# Token.net
KiCad netlist of a schematic drawn in EAGLE
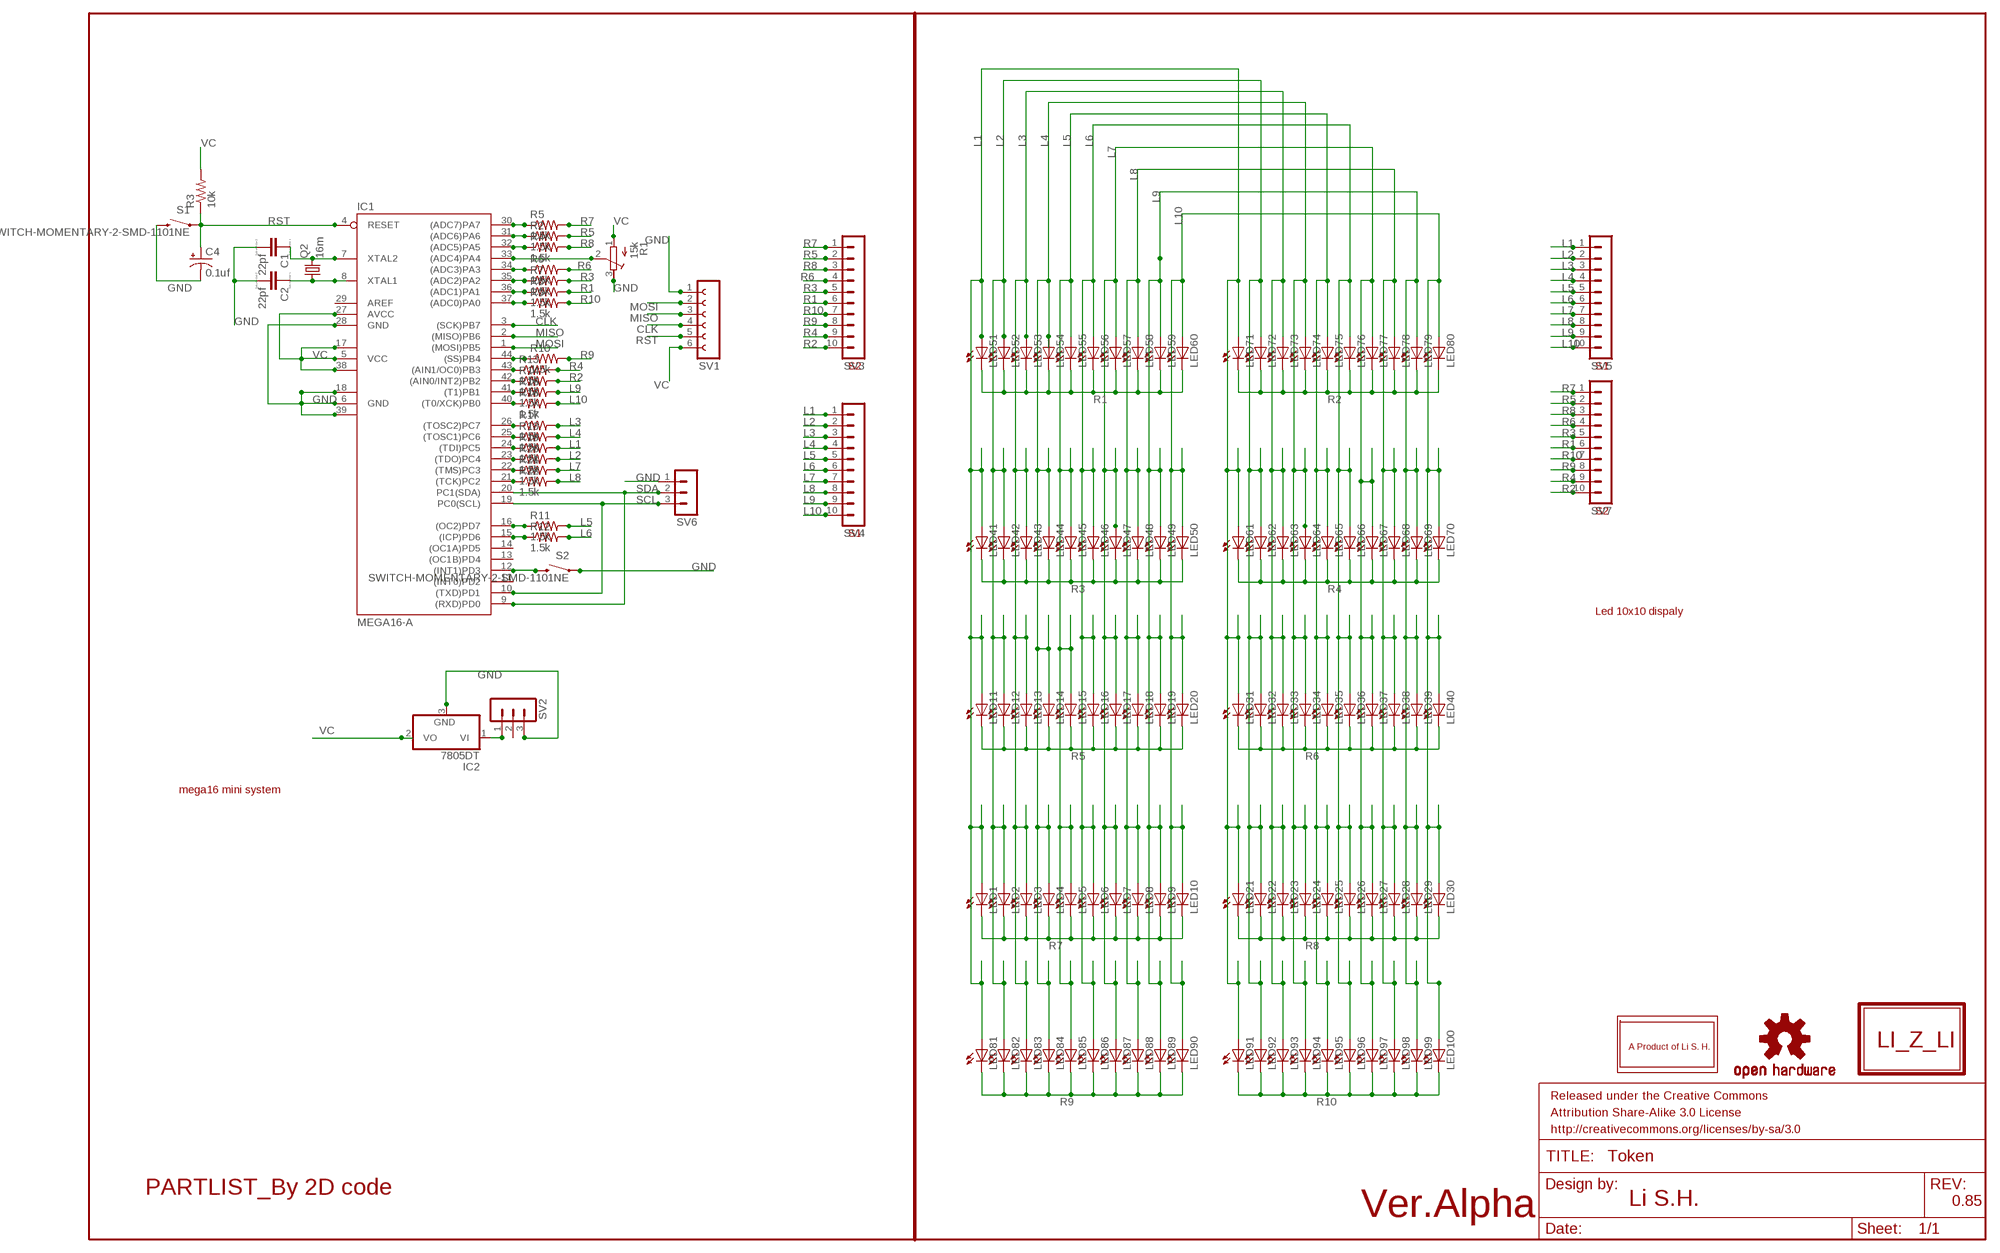
[diagram p0: schematic, sheet 1]

(export (version "E")
  (design (tool "Eeschema 10.0.6"))
  (components
    (comp (ref "C1")
      (value "22pf")
      (footprint "eagle-import:C0402")
      (libsource (lib "eagle-import") (part "CC0402"))
    )
    (comp (ref "C2")
      (value "22pf")
      (footprint "eagle-import:C0402")
      (libsource (lib "eagle-import") (part "CC0402"))
    )
    (comp (ref "C4")
      (value "0.1uf")
      (footprint "eagle-import:D_7343-31W")
      (libsource (lib "eagle-import") (part "CPOL-USD/7343-31W"))
    )
    (comp (ref "FRAME1")
      (value "FRAME-LEDGER")
      (footprint "eagle-import:CREATIVE_COMMONS")
      (libsource (lib "eagle-import") (part "FRAME-LEDGER"))
    )
    (comp (ref "IC1")
      (value "MEGA16-A")
      (footprint "eagle-import:TQFP44")
      (fields (field (name "MPN") "ATMEGA16-16AU"))
      (libsource (lib "eagle-import") (part "MEGA16-A"))
    )
    (comp (ref "IC2")
      (value "7805DT")
      (footprint "eagle-import:TO252")
      (libsource (lib "eagle-import") (part "78DT05"))
    )
    (comp (ref "LED1")
      (value "LEDCHIPLED_0805")
      (footprint "eagle-import:CHIPLED_0805")
      (libsource (lib "eagle-import") (part "LEDCHIPLED_0805"))
    )
    (comp (ref "LED2")
      (value "LEDCHIPLED_0805")
      (footprint "eagle-import:CHIPLED_0805")
      (libsource (lib "eagle-import") (part "LEDCHIPLED_0805"))
    )
    (comp (ref "LED3")
      (value "LEDCHIPLED_0805")
      (footprint "eagle-import:CHIPLED_0805")
      (libsource (lib "eagle-import") (part "LEDCHIPLED_0805"))
    )
    (comp (ref "LED4")
      (value "LEDCHIPLED_0805")
      (footprint "eagle-import:CHIPLED_0805")
      (libsource (lib "eagle-import") (part "LEDCHIPLED_0805"))
    )
    (comp (ref "LED5")
      (value "LEDCHIPLED_0805")
      (footprint "eagle-import:CHIPLED_0805")
      (libsource (lib "eagle-import") (part "LEDCHIPLED_0805"))
    )
    (comp (ref "LED6")
      (value "LEDCHIPLED_0805")
      (footprint "eagle-import:CHIPLED_0805")
      (libsource (lib "eagle-import") (part "LEDCHIPLED_0805"))
    )
    (comp (ref "LED7")
      (value "LEDCHIPLED_0805")
      (footprint "eagle-import:CHIPLED_0805")
      (libsource (lib "eagle-import") (part "LEDCHIPLED_0805"))
    )
    (comp (ref "LED8")
      (value "LEDCHIPLED_0805")
      (footprint "eagle-import:CHIPLED_0805")
      (libsource (lib "eagle-import") (part "LEDCHIPLED_0805"))
    )
    (comp (ref "LED9")
      (value "LEDCHIPLED_0805")
      (footprint "eagle-import:CHIPLED_0805")
      (libsource (lib "eagle-import") (part "LEDCHIPLED_0805"))
    )
    (comp (ref "LED10")
      (value "LEDCHIPLED_0805")
      (footprint "eagle-import:CHIPLED_0805")
      (libsource (lib "eagle-import") (part "LEDCHIPLED_0805"))
    )
    (comp (ref "LED11")
      (value "LEDCHIPLED_0805")
      (footprint "eagle-import:CHIPLED_0805")
      (libsource (lib "eagle-import") (part "LEDCHIPLED_0805"))
    )
    (comp (ref "LED12")
      (value "LEDCHIPLED_0805")
      (footprint "eagle-import:CHIPLED_0805")
      (libsource (lib "eagle-import") (part "LEDCHIPLED_0805"))
    )
    (comp (ref "LED13")
      (value "LEDCHIPLED_0805")
      (footprint "eagle-import:CHIPLED_0805")
      (libsource (lib "eagle-import") (part "LEDCHIPLED_0805"))
    )
    (comp (ref "LED14")
      (value "LEDCHIPLED_0805")
      (footprint "eagle-import:CHIPLED_0805")
      (libsource (lib "eagle-import") (part "LEDCHIPLED_0805"))
    )
    (comp (ref "LED15")
      (value "LEDCHIPLED_0805")
      (footprint "eagle-import:CHIPLED_0805")
      (libsource (lib "eagle-import") (part "LEDCHIPLED_0805"))
    )
    (comp (ref "LED16")
      (value "LEDCHIPLED_0805")
      (footprint "eagle-import:CHIPLED_0805")
      (libsource (lib "eagle-import") (part "LEDCHIPLED_0805"))
    )
    (comp (ref "LED17")
      (value "LEDCHIPLED_0805")
      (footprint "eagle-import:CHIPLED_0805")
      (libsource (lib "eagle-import") (part "LEDCHIPLED_0805"))
    )
    (comp (ref "LED18")
      (value "LEDCHIPLED_0805")
      (footprint "eagle-import:CHIPLED_0805")
      (libsource (lib "eagle-import") (part "LEDCHIPLED_0805"))
    )
    (comp (ref "LED19")
      (value "LEDCHIPLED_0805")
      (footprint "eagle-import:CHIPLED_0805")
      (libsource (lib "eagle-import") (part "LEDCHIPLED_0805"))
    )
    (comp (ref "LED20")
      (value "LEDCHIPLED_0805")
      (footprint "eagle-import:CHIPLED_0805")
      (libsource (lib "eagle-import") (part "LEDCHIPLED_0805"))
    )
    (comp (ref "LED21")
      (value "LEDCHIPLED_0805")
      (footprint "eagle-import:CHIPLED_0805")
      (libsource (lib "eagle-import") (part "LEDCHIPLED_0805"))
    )
    (comp (ref "LED22")
      (value "LEDCHIPLED_0805")
      (footprint "eagle-import:CHIPLED_0805")
      (libsource (lib "eagle-import") (part "LEDCHIPLED_0805"))
    )
    (comp (ref "LED23")
      (value "LEDCHIPLED_0805")
      (footprint "eagle-import:CHIPLED_0805")
      (libsource (lib "eagle-import") (part "LEDCHIPLED_0805"))
    )
    (comp (ref "LED24")
      (value "LEDCHIPLED_0805")
      (footprint "eagle-import:CHIPLED_0805")
      (libsource (lib "eagle-import") (part "LEDCHIPLED_0805"))
    )
    (comp (ref "LED25")
      (value "LEDCHIPLED_0805")
      (footprint "eagle-import:CHIPLED_0805")
      (libsource (lib "eagle-import") (part "LEDCHIPLED_0805"))
    )
    (comp (ref "LED26")
      (value "LEDCHIPLED_0805")
      (footprint "eagle-import:CHIPLED_0805")
      (libsource (lib "eagle-import") (part "LEDCHIPLED_0805"))
    )
    (comp (ref "LED27")
      (value "LEDCHIPLED_0805")
      (footprint "eagle-import:CHIPLED_0805")
      (libsource (lib "eagle-import") (part "LEDCHIPLED_0805"))
    )
    (comp (ref "LED28")
      (value "LEDCHIPLED_0805")
      (footprint "eagle-import:CHIPLED_0805")
      (libsource (lib "eagle-import") (part "LEDCHIPLED_0805"))
    )
    (comp (ref "LED29")
      (value "LEDCHIPLED_0805")
      (footprint "eagle-import:CHIPLED_0805")
      (libsource (lib "eagle-import") (part "LEDCHIPLED_0805"))
    )
    (comp (ref "LED30")
      (value "LEDCHIPLED_0805")
      (footprint "eagle-import:CHIPLED_0805")
      (libsource (lib "eagle-import") (part "LEDCHIPLED_0805"))
    )
    (comp (ref "LED31")
      (value "LEDCHIPLED_0805")
      (footprint "eagle-import:CHIPLED_0805")
      (libsource (lib "eagle-import") (part "LEDCHIPLED_0805"))
    )
    (comp (ref "LED32")
      (value "LEDCHIPLED_0805")
      (footprint "eagle-import:CHIPLED_0805")
      (libsource (lib "eagle-import") (part "LEDCHIPLED_0805"))
    )
    (comp (ref "LED33")
      (value "LEDCHIPLED_0805")
      (footprint "eagle-import:CHIPLED_0805")
      (libsource (lib "eagle-import") (part "LEDCHIPLED_0805"))
    )
    (comp (ref "LED34")
      (value "LEDCHIPLED_0805")
      (footprint "eagle-import:CHIPLED_0805")
      (libsource (lib "eagle-import") (part "LEDCHIPLED_0805"))
    )
    (comp (ref "LED35")
      (value "LEDCHIPLED_0805")
      (footprint "eagle-import:CHIPLED_0805")
      (libsource (lib "eagle-import") (part "LEDCHIPLED_0805"))
    )
    (comp (ref "LED36")
      (value "LEDCHIPLED_0805")
      (footprint "eagle-import:CHIPLED_0805")
      (libsource (lib "eagle-import") (part "LEDCHIPLED_0805"))
    )
    (comp (ref "LED37")
      (value "LEDCHIPLED_0805")
      (footprint "eagle-import:CHIPLED_0805")
      (libsource (lib "eagle-import") (part "LEDCHIPLED_0805"))
    )
    (comp (ref "LED38")
      (value "LEDCHIPLED_0805")
      (footprint "eagle-import:CHIPLED_0805")
      (libsource (lib "eagle-import") (part "LEDCHIPLED_0805"))
    )
    (comp (ref "LED39")
      (value "LEDCHIPLED_0805")
      (footprint "eagle-import:CHIPLED_0805")
      (libsource (lib "eagle-import") (part "LEDCHIPLED_0805"))
    )
    (comp (ref "LED40")
      (value "LEDCHIPLED_0805")
      (footprint "eagle-import:CHIPLED_0805")
      (libsource (lib "eagle-import") (part "LEDCHIPLED_0805"))
    )
    (comp (ref "LED41")
      (value "LEDCHIPLED_0805")
      (footprint "eagle-import:CHIPLED_0805")
      (libsource (lib "eagle-import") (part "LEDCHIPLED_0805"))
    )
    (comp (ref "LED42")
      (value "LEDCHIPLED_0805")
      (footprint "eagle-import:CHIPLED_0805")
      (libsource (lib "eagle-import") (part "LEDCHIPLED_0805"))
    )
    (comp (ref "LED43")
      (value "LEDCHIPLED_0805")
      (footprint "eagle-import:CHIPLED_0805")
      (libsource (lib "eagle-import") (part "LEDCHIPLED_0805"))
    )
    (comp (ref "LED44")
      (value "LEDCHIPLED_0805")
      (footprint "eagle-import:CHIPLED_0805")
      (libsource (lib "eagle-import") (part "LEDCHIPLED_0805"))
    )
    (comp (ref "LED45")
      (value "LEDCHIPLED_0805")
      (footprint "eagle-import:CHIPLED_0805")
      (libsource (lib "eagle-import") (part "LEDCHIPLED_0805"))
    )
    (comp (ref "LED46")
      (value "LEDCHIPLED_0805")
      (footprint "eagle-import:CHIPLED_0805")
      (libsource (lib "eagle-import") (part "LEDCHIPLED_0805"))
    )
    (comp (ref "LED47")
      (value "LEDCHIPLED_0805")
      (footprint "eagle-import:CHIPLED_0805")
      (libsource (lib "eagle-import") (part "LEDCHIPLED_0805"))
    )
    (comp (ref "LED48")
      (value "LEDCHIPLED_0805")
      (footprint "eagle-import:CHIPLED_0805")
      (libsource (lib "eagle-import") (part "LEDCHIPLED_0805"))
    )
    (comp (ref "LED49")
      (value "LEDCHIPLED_0805")
      (footprint "eagle-import:CHIPLED_0805")
      (libsource (lib "eagle-import") (part "LEDCHIPLED_0805"))
    )
    (comp (ref "LED50")
      (value "LEDCHIPLED_0805")
      (footprint "eagle-import:CHIPLED_0805")
      (libsource (lib "eagle-import") (part "LEDCHIPLED_0805"))
    )
    (comp (ref "LED51")
      (value "LEDCHIPLED_0805")
      (footprint "eagle-import:CHIPLED_0805")
      (libsource (lib "eagle-import") (part "LEDCHIPLED_0805"))
    )
    (comp (ref "LED52")
      (value "LEDCHIPLED_0805")
      (footprint "eagle-import:CHIPLED_0805")
      (libsource (lib "eagle-import") (part "LEDCHIPLED_0805"))
    )
    (comp (ref "LED53")
      (value "LEDCHIPLED_0805")
      (footprint "eagle-import:CHIPLED_0805")
      (libsource (lib "eagle-import") (part "LEDCHIPLED_0805"))
    )
    (comp (ref "LED54")
      (value "LEDCHIPLED_0805")
      (footprint "eagle-import:CHIPLED_0805")
      (libsource (lib "eagle-import") (part "LEDCHIPLED_0805"))
    )
    (comp (ref "LED55")
      (value "LEDCHIPLED_0805")
      (footprint "eagle-import:CHIPLED_0805")
      (libsource (lib "eagle-import") (part "LEDCHIPLED_0805"))
    )
    (comp (ref "LED56")
      (value "LEDCHIPLED_0805")
      (footprint "eagle-import:CHIPLED_0805")
      (libsource (lib "eagle-import") (part "LEDCHIPLED_0805"))
    )
    (comp (ref "LED57")
      (value "LEDCHIPLED_0805")
      (footprint "eagle-import:CHIPLED_0805")
      (libsource (lib "eagle-import") (part "LEDCHIPLED_0805"))
    )
    (comp (ref "LED58")
      (value "LEDCHIPLED_0805")
      (footprint "eagle-import:CHIPLED_0805")
      (libsource (lib "eagle-import") (part "LEDCHIPLED_0805"))
    )
    (comp (ref "LED59")
      (value "LEDCHIPLED_0805")
      (footprint "eagle-import:CHIPLED_0805")
      (libsource (lib "eagle-import") (part "LEDCHIPLED_0805"))
    )
    (comp (ref "LED60")
      (value "LEDCHIPLED_0805")
      (footprint "eagle-import:CHIPLED_0805")
      (libsource (lib "eagle-import") (part "LEDCHIPLED_0805"))
    )
    (comp (ref "LED61")
      (value "LEDCHIPLED_0805")
      (footprint "eagle-import:CHIPLED_0805")
      (libsource (lib "eagle-import") (part "LEDCHIPLED_0805"))
    )
    (comp (ref "LED62")
      (value "LEDCHIPLED_0805")
      (footprint "eagle-import:CHIPLED_0805")
      (libsource (lib "eagle-import") (part "LEDCHIPLED_0805"))
    )
    (comp (ref "LED63")
      (value "LEDCHIPLED_0805")
      (footprint "eagle-import:CHIPLED_0805")
      (libsource (lib "eagle-import") (part "LEDCHIPLED_0805"))
    )
    (comp (ref "LED64")
      (value "LEDCHIPLED_0805")
      (footprint "eagle-import:CHIPLED_0805")
      (libsource (lib "eagle-import") (part "LEDCHIPLED_0805"))
    )
    (comp (ref "LED65")
      (value "LEDCHIPLED_0805")
      (footprint "eagle-import:CHIPLED_0805")
      (libsource (lib "eagle-import") (part "LEDCHIPLED_0805"))
    )
    (comp (ref "LED66")
      (value "LEDCHIPLED_0805")
      (footprint "eagle-import:CHIPLED_0805")
      (libsource (lib "eagle-import") (part "LEDCHIPLED_0805"))
    )
    (comp (ref "LED67")
      (value "LEDCHIPLED_0805")
      (footprint "eagle-import:CHIPLED_0805")
      (libsource (lib "eagle-import") (part "LEDCHIPLED_0805"))
    )
    (comp (ref "LED68")
      (value "LEDCHIPLED_0805")
      (footprint "eagle-import:CHIPLED_0805")
      (libsource (lib "eagle-import") (part "LEDCHIPLED_0805"))
    )
    (comp (ref "LED69")
      (value "LEDCHIPLED_0805")
      (footprint "eagle-import:CHIPLED_0805")
      (libsource (lib "eagle-import") (part "LEDCHIPLED_0805"))
    )
    (comp (ref "LED70")
      (value "LEDCHIPLED_0805")
      (footprint "eagle-import:CHIPLED_0805")
      (libsource (lib "eagle-import") (part "LEDCHIPLED_0805"))
    )
    (comp (ref "LED71")
      (value "LEDCHIPLED_0805")
      (footprint "eagle-import:CHIPLED_0805")
      (libsource (lib "eagle-import") (part "LEDCHIPLED_0805"))
    )
    (comp (ref "LED72")
      (value "LEDCHIPLED_0805")
      (footprint "eagle-import:CHIPLED_0805")
      (libsource (lib "eagle-import") (part "LEDCHIPLED_0805"))
    )
    (comp (ref "LED73")
      (value "LEDCHIPLED_0805")
      (footprint "eagle-import:CHIPLED_0805")
      (libsource (lib "eagle-import") (part "LEDCHIPLED_0805"))
    )
    (comp (ref "LED74")
      (value "LEDCHIPLED_0805")
      (footprint "eagle-import:CHIPLED_0805")
      (libsource (lib "eagle-import") (part "LEDCHIPLED_0805"))
    )
    (comp (ref "LED75")
      (value "LEDCHIPLED_0805")
      (footprint "eagle-import:CHIPLED_0805")
      (libsource (lib "eagle-import") (part "LEDCHIPLED_0805"))
    )
    (comp (ref "LED76")
      (value "LEDCHIPLED_0805")
      (footprint "eagle-import:CHIPLED_0805")
      (libsource (lib "eagle-import") (part "LEDCHIPLED_0805"))
    )
    (comp (ref "LED77")
      (value "LEDCHIPLED_0805")
      (footprint "eagle-import:CHIPLED_0805")
      (libsource (lib "eagle-import") (part "LEDCHIPLED_0805"))
    )
    (comp (ref "LED78")
      (value "LEDCHIPLED_0805")
      (footprint "eagle-import:CHIPLED_0805")
      (libsource (lib "eagle-import") (part "LEDCHIPLED_0805"))
    )
    (comp (ref "LED79")
      (value "LEDCHIPLED_0805")
      (footprint "eagle-import:CHIPLED_0805")
      (libsource (lib "eagle-import") (part "LEDCHIPLED_0805"))
    )
    (comp (ref "LED80")
      (value "LEDCHIPLED_0805")
      (footprint "eagle-import:CHIPLED_0805")
      (libsource (lib "eagle-import") (part "LEDCHIPLED_0805"))
    )
    (comp (ref "LED81")
      (value "LEDCHIPLED_0805")
      (footprint "eagle-import:CHIPLED_0805")
      (libsource (lib "eagle-import") (part "LEDCHIPLED_0805"))
    )
    (comp (ref "LED82")
      (value "LEDCHIPLED_0805")
      (footprint "eagle-import:CHIPLED_0805")
      (libsource (lib "eagle-import") (part "LEDCHIPLED_0805"))
    )
    (comp (ref "LED83")
      (value "LEDCHIPLED_0805")
      (footprint "eagle-import:CHIPLED_0805")
      (libsource (lib "eagle-import") (part "LEDCHIPLED_0805"))
    )
    (comp (ref "LED84")
      (value "LEDCHIPLED_0805")
      (footprint "eagle-import:CHIPLED_0805")
      (libsource (lib "eagle-import") (part "LEDCHIPLED_0805"))
    )
    (comp (ref "LED85")
      (value "LEDCHIPLED_0805")
      (footprint "eagle-import:CHIPLED_0805")
      (libsource (lib "eagle-import") (part "LEDCHIPLED_0805"))
    )
    (comp (ref "LED86")
      (value "LEDCHIPLED_0805")
      (footprint "eagle-import:CHIPLED_0805")
      (libsource (lib "eagle-import") (part "LEDCHIPLED_0805"))
    )
    (comp (ref "LED87")
      (value "LEDCHIPLED_0805")
      (footprint "eagle-import:CHIPLED_0805")
      (libsource (lib "eagle-import") (part "LEDCHIPLED_0805"))
    )
    (comp (ref "LED88")
      (value "LEDCHIPLED_0805")
      (footprint "eagle-import:CHIPLED_0805")
      (libsource (lib "eagle-import") (part "LEDCHIPLED_0805"))
    )
    (comp (ref "LED89")
      (value "LEDCHIPLED_0805")
      (footprint "eagle-import:CHIPLED_0805")
      (libsource (lib "eagle-import") (part "LEDCHIPLED_0805"))
    )
    (comp (ref "LED90")
      (value "LEDCHIPLED_0805")
      (footprint "eagle-import:CHIPLED_0805")
      (libsource (lib "eagle-import") (part "LEDCHIPLED_0805"))
    )
    (comp (ref "LED91")
      (value "LEDCHIPLED_0805")
      (footprint "eagle-import:CHIPLED_0805")
      (libsource (lib "eagle-import") (part "LEDCHIPLED_0805"))
    )
    (comp (ref "LED92")
      (value "LEDCHIPLED_0805")
      (footprint "eagle-import:CHIPLED_0805")
      (libsource (lib "eagle-import") (part "LEDCHIPLED_0805"))
    )
    (comp (ref "LED93")
      (value "LEDCHIPLED_0805")
      (footprint "eagle-import:CHIPLED_0805")
      (libsource (lib "eagle-import") (part "LEDCHIPLED_0805"))
    )
    (comp (ref "LED94")
      (value "LEDCHIPLED_0805")
      (footprint "eagle-import:CHIPLED_0805")
      (libsource (lib "eagle-import") (part "LEDCHIPLED_0805"))
    )
    (comp (ref "LED95")
      (value "LEDCHIPLED_0805")
      (footprint "eagle-import:CHIPLED_0805")
      (libsource (lib "eagle-import") (part "LEDCHIPLED_0805"))
    )
    (comp (ref "LED96")
      (value "LEDCHIPLED_0805")
      (footprint "eagle-import:CHIPLED_0805")
      (libsource (lib "eagle-import") (part "LEDCHIPLED_0805"))
    )
    (comp (ref "LED97")
      (value "LEDCHIPLED_0805")
      (footprint "eagle-import:CHIPLED_0805")
      (libsource (lib "eagle-import") (part "LEDCHIPLED_0805"))
    )
    (comp (ref "LED98")
      (value "LEDCHIPLED_0805")
      (footprint "eagle-import:CHIPLED_0805")
      (libsource (lib "eagle-import") (part "LEDCHIPLED_0805"))
    )
    (comp (ref "LED99")
      (value "LEDCHIPLED_0805")
      (footprint "eagle-import:CHIPLED_0805")
      (libsource (lib "eagle-import") (part "LEDCHIPLED_0805"))
    )
    (comp (ref "LED100")
      (value "LEDCHIPLED_0805")
      (footprint "eagle-import:CHIPLED_0805")
      (libsource (lib "eagle-import") (part "LEDCHIPLED_0805"))
    )
    (comp (ref "LOGO1")
      (value "OSHW-LOGOS")
      (footprint "eagle-import:OSHW-LOGO-S")
      (libsource (lib "eagle-import") (part "OSHW-LOGOS"))
    )
    (comp (ref "Q2")
      (value "16m")
      (footprint "eagle-import:HC49UP")
      (libsource (lib "eagle-import") (part "CRYSTALHC49UP"))
    )
    (comp (ref "R1")
      (value "15k")
      (footprint "eagle-import:RTRIM64W")
      (libsource (lib "eagle-import") (part "R-TRIMM64W"))
    )
    (comp (ref "R2")
      (value "1.5k")
      (footprint "eagle-import:R0201")
      (libsource (lib "eagle-import") (part "R-US_R0201"))
    )
    (comp (ref "R3")
      (value "10k")
      (footprint "eagle-import:R0201")
      (libsource (lib "eagle-import") (part "R-US_R0201"))
    )
    (comp (ref "R4")
      (value "1.5k")
      (footprint "eagle-import:R0201")
      (libsource (lib "eagle-import") (part "R-US_R0201"))
    )
    (comp (ref "R5")
      (value "1.5k")
      (footprint "eagle-import:R0201")
      (libsource (lib "eagle-import") (part "R-US_R0201"))
    )
    (comp (ref "R6")
      (value "1.5k")
      (footprint "eagle-import:R0201")
      (libsource (lib "eagle-import") (part "R-US_R0201"))
    )
    (comp (ref "R7")
      (value "1.5k")
      (footprint "eagle-import:R0201")
      (libsource (lib "eagle-import") (part "R-US_R0201"))
    )
    (comp (ref "R8")
      (value "1.5k")
      (footprint "eagle-import:R0201")
      (libsource (lib "eagle-import") (part "R-US_R0201"))
    )
    (comp (ref "R9")
      (value "1.5k")
      (footprint "eagle-import:R0201")
      (libsource (lib "eagle-import") (part "R-US_R0201"))
    )
    (comp (ref "R10")
      (value "1.5k")
      (footprint "eagle-import:R0201")
      (libsource (lib "eagle-import") (part "R-US_R0201"))
    )
    (comp (ref "R11")
      (value "1.5k")
      (footprint "eagle-import:R0201")
      (libsource (lib "eagle-import") (part "R-US_R0201"))
    )
    (comp (ref "R12")
      (value "1.5k")
      (footprint "eagle-import:R0201")
      (libsource (lib "eagle-import") (part "R-US_R0201"))
    )
    (comp (ref "R13")
      (value "1.5k")
      (footprint "eagle-import:R0201")
      (libsource (lib "eagle-import") (part "R-US_R0201"))
    )
    (comp (ref "R14")
      (value "1.5k")
      (footprint "eagle-import:R0201")
      (libsource (lib "eagle-import") (part "R-US_R0201"))
    )
    (comp (ref "R15")
      (value "1.5k")
      (footprint "eagle-import:R0201")
      (libsource (lib "eagle-import") (part "R-US_R0201"))
    )
    (comp (ref "R16")
      (value "1.5k")
      (footprint "eagle-import:R0201")
      (libsource (lib "eagle-import") (part "R-US_R0201"))
    )
    (comp (ref "R17")
      (value "1.5k")
      (footprint "eagle-import:R0201")
      (libsource (lib "eagle-import") (part "R-US_R0201"))
    )
    (comp (ref "R18")
      (value "1.5k")
      (footprint "eagle-import:R0201")
      (libsource (lib "eagle-import") (part "R-US_R0201"))
    )
    (comp (ref "R19")
      (value "1.5k")
      (footprint "eagle-import:R0201")
      (libsource (lib "eagle-import") (part "R-US_R0201"))
    )
    (comp (ref "R20")
      (value "1.5k")
      (footprint "eagle-import:R0201")
      (libsource (lib "eagle-import") (part "R-US_R0201"))
    )
    (comp (ref "R21")
      (value "1.5k")
      (footprint "eagle-import:R0201")
      (libsource (lib "eagle-import") (part "R-US_R0201"))
    )
    (comp (ref "R22")
      (value "1.5k")
      (footprint "eagle-import:R0201")
      (libsource (lib "eagle-import") (part "R-US_R0201"))
    )
    (comp (ref "S1")
      (value "SWITCH-MOMENTARY-2-SMD-1101NE")
      (footprint "eagle-import:TACTILE-SWITCH-1101NE")
      (libsource (lib "eagle-import") (part "SWITCH-MOMENTARY-2-SMD-1101NE"))
    )
    (comp (ref "S2")
      (value "SWITCH-MOMENTARY-2-SMD-1101NE")
      (footprint "eagle-import:TACTILE-SWITCH-1101NE")
      (libsource (lib "eagle-import") (part "SWITCH-MOMENTARY-2-SMD-1101NE"))
    )
    (comp (ref "SV1")
      (value "FE06-1")
      (footprint "eagle-import:FE06")
      (libsource (lib "eagle-import") (part "FE06-1"))
    )
    (comp (ref "SV2")
      (value "MA03-1")
      (footprint "eagle-import:MA03-1")
      (libsource (lib "eagle-import") (part "MA03-1"))
    )
    (comp (ref "SV3")
      (value "MA10-1")
      (footprint "eagle-import:MA10-1")
      (libsource (lib "eagle-import") (part "MA10-1"))
    )
    (comp (ref "SV4")
      (value "MA10-1")
      (footprint "eagle-import:MA10-1")
      (libsource (lib "eagle-import") (part "MA10-1"))
    )
    (comp (ref "SV5")
      (value "MA10-1")
      (footprint "eagle-import:MA10-1")
      (libsource (lib "eagle-import") (part "MA10-1"))
    )
    (comp (ref "SV6")
      (value "MA03-1")
      (footprint "eagle-import:MA03-1")
      (libsource (lib "eagle-import") (part "MA03-1"))
    )
    (comp (ref "SV7")
      (value "MA10-1")
      (footprint "eagle-import:MA10-1")
      (libsource (lib "eagle-import") (part "MA10-1"))
    )
    (comp (ref "U$1")
      (value "NO1")
      (footprint "eagle-import:NO1")
      (libsource (lib "eagle-import") (part "NO1"))
    )
    (comp (ref "U$2")
      (value "NO2")
      (footprint "eagle-import:NO2")
      (libsource (lib "eagle-import") (part "NO2"))
    )
    (comp (ref "U$3")
      (value "VERALPHA")
      (footprint "eagle-import:VERALPHA")
      (libsource (lib "eagle-import") (part "VERALPHA"))
    )
    (comp (ref "U$4")
      (value "PARTIST-2DCODE")
      (footprint "eagle-import:PARTLIST-2DCODE")
      (libsource (lib "eagle-import") (part "PARTIST-2DCODE"))
    )
  )
  (nets
    (net (code "1") (name "/CLK") (class "Default")
      (node (ref "IC1") (pin "3") (pinfunction "(SCK)PB7_3") (pintype "bidirectional"))
      (node (ref "SV1") (pin "4") (pinfunction "4_4") (pintype "passive"))
    )
    (net (code "2") (name "/GND") (class "Default")
      (node (ref "C1") (pin "2") (pinfunction "2_2") (pintype "passive"))
      (node (ref "C2") (pin "2") (pinfunction "2_2") (pintype "passive"))
      (node (ref "C4") (pin "-") (pinfunction "-_-") (pintype "passive"))
      (node (ref "IC1") (pin "18") (pinfunction "GND1_18") (pintype "power_in"))
      (node (ref "IC1") (pin "28") (pinfunction "GND_28") (pintype "power_in"))
      (node (ref "IC1") (pin "39") (pinfunction "GND2_39") (pintype "power_in"))
      (node (ref "IC1") (pin "6") (pinfunction "GND_6") (pintype "power_in"))
      (node (ref "IC2") (pin "3") (pinfunction "GND_3") (pintype "passive"))
      (node (ref "R1") (pin "3") (pinfunction "A_3") (pintype "passive"))
      (node (ref "S1") (pin "P$2") (pinfunction "2_P$2") (pintype "passive"))
      (node (ref "S2") (pin "P$1") (pinfunction "1_P$1") (pintype "passive"))
      (node (ref "SV1") (pin "1") (pinfunction "1_1") (pintype "passive"))
      (node (ref "SV2") (pin "3") (pinfunction "3_3") (pintype "passive"))
      (node (ref "SV6") (pin "1") (pinfunction "1_1") (pintype "passive"))
    )
    (net (code "3") (name "/L1") (class "Default")
      (node (ref "LED1") (pin "A") (pinfunction "A_A") (pintype "passive"))
      (node (ref "LED11") (pin "A") (pinfunction "A_A") (pintype "passive"))
      (node (ref "LED21") (pin "A") (pinfunction "A_A") (pintype "passive"))
      (node (ref "LED31") (pin "A") (pinfunction "A_A") (pintype "passive"))
      (node (ref "LED41") (pin "A") (pinfunction "A_A") (pintype "passive"))
      (node (ref "LED51") (pin "A") (pinfunction "A_A") (pintype "passive"))
      (node (ref "LED61") (pin "A") (pinfunction "A_A") (pintype "passive"))
      (node (ref "LED71") (pin "A") (pinfunction "A_A") (pintype "passive"))
      (node (ref "LED81") (pin "A") (pinfunction "A_A") (pintype "passive"))
      (node (ref "LED91") (pin "A") (pinfunction "A_A") (pintype "passive"))
      (node (ref "SV5") (pin "1") (pinfunction "1_1") (pintype "passive"))
    )
    (net (code "4") (name "/L2") (class "Default")
      (node (ref "LED12") (pin "A") (pinfunction "A_A") (pintype "passive"))
      (node (ref "LED2") (pin "A") (pinfunction "A_A") (pintype "passive"))
      (node (ref "LED22") (pin "A") (pinfunction "A_A") (pintype "passive"))
      (node (ref "LED32") (pin "A") (pinfunction "A_A") (pintype "passive"))
      (node (ref "LED42") (pin "A") (pinfunction "A_A") (pintype "passive"))
      (node (ref "LED52") (pin "A") (pinfunction "A_A") (pintype "passive"))
      (node (ref "LED62") (pin "A") (pinfunction "A_A") (pintype "passive"))
      (node (ref "LED72") (pin "A") (pinfunction "A_A") (pintype "passive"))
      (node (ref "LED82") (pin "A") (pinfunction "A_A") (pintype "passive"))
      (node (ref "LED92") (pin "A") (pinfunction "A_A") (pintype "passive"))
      (node (ref "SV5") (pin "2") (pinfunction "2_2") (pintype "passive"))
    )
    (net (code "5") (name "/L3") (class "Default")
      (node (ref "LED13") (pin "A") (pinfunction "A_A") (pintype "passive"))
      (node (ref "LED23") (pin "A") (pinfunction "A_A") (pintype "passive"))
      (node (ref "LED3") (pin "A") (pinfunction "A_A") (pintype "passive"))
      (node (ref "LED33") (pin "A") (pinfunction "A_A") (pintype "passive"))
      (node (ref "LED43") (pin "A") (pinfunction "A_A") (pintype "passive"))
      (node (ref "LED53") (pin "A") (pinfunction "A_A") (pintype "passive"))
      (node (ref "LED63") (pin "A") (pinfunction "A_A") (pintype "passive"))
      (node (ref "LED73") (pin "A") (pinfunction "A_A") (pintype "passive"))
      (node (ref "LED83") (pin "A") (pinfunction "A_A") (pintype "passive"))
      (node (ref "LED93") (pin "A") (pinfunction "A_A") (pintype "passive"))
      (node (ref "SV5") (pin "3") (pinfunction "3_3") (pintype "passive"))
    )
    (net (code "6") (name "/L4") (class "Default")
      (node (ref "LED14") (pin "A") (pinfunction "A_A") (pintype "passive"))
      (node (ref "LED24") (pin "A") (pinfunction "A_A") (pintype "passive"))
      (node (ref "LED34") (pin "A") (pinfunction "A_A") (pintype "passive"))
      (node (ref "LED4") (pin "A") (pinfunction "A_A") (pintype "passive"))
      (node (ref "LED44") (pin "A") (pinfunction "A_A") (pintype "passive"))
      (node (ref "LED54") (pin "A") (pinfunction "A_A") (pintype "passive"))
      (node (ref "LED64") (pin "A") (pinfunction "A_A") (pintype "passive"))
      (node (ref "LED74") (pin "A") (pinfunction "A_A") (pintype "passive"))
      (node (ref "LED84") (pin "A") (pinfunction "A_A") (pintype "passive"))
      (node (ref "LED94") (pin "A") (pinfunction "A_A") (pintype "passive"))
      (node (ref "SV5") (pin "4") (pinfunction "4_4") (pintype "passive"))
    )
    (net (code "7") (name "/L5") (class "Default")
      (node (ref "LED15") (pin "A") (pinfunction "A_A") (pintype "passive"))
      (node (ref "LED25") (pin "A") (pinfunction "A_A") (pintype "passive"))
      (node (ref "LED35") (pin "A") (pinfunction "A_A") (pintype "passive"))
      (node (ref "LED45") (pin "A") (pinfunction "A_A") (pintype "passive"))
      (node (ref "LED5") (pin "A") (pinfunction "A_A") (pintype "passive"))
      (node (ref "LED55") (pin "A") (pinfunction "A_A") (pintype "passive"))
      (node (ref "LED65") (pin "A") (pinfunction "A_A") (pintype "passive"))
      (node (ref "LED75") (pin "A") (pinfunction "A_A") (pintype "passive"))
      (node (ref "LED85") (pin "A") (pinfunction "A_A") (pintype "passive"))
      (node (ref "LED95") (pin "A") (pinfunction "A_A") (pintype "passive"))
      (node (ref "SV5") (pin "5") (pinfunction "5_5") (pintype "passive"))
    )
    (net (code "8") (name "/L6") (class "Default")
      (node (ref "LED16") (pin "A") (pinfunction "A_A") (pintype "passive"))
      (node (ref "LED26") (pin "A") (pinfunction "A_A") (pintype "passive"))
      (node (ref "LED36") (pin "A") (pinfunction "A_A") (pintype "passive"))
      (node (ref "LED46") (pin "A") (pinfunction "A_A") (pintype "passive"))
      (node (ref "LED56") (pin "A") (pinfunction "A_A") (pintype "passive"))
      (node (ref "LED6") (pin "A") (pinfunction "A_A") (pintype "passive"))
      (node (ref "LED66") (pin "A") (pinfunction "A_A") (pintype "passive"))
      (node (ref "LED76") (pin "A") (pinfunction "A_A") (pintype "passive"))
      (node (ref "LED86") (pin "A") (pinfunction "A_A") (pintype "passive"))
      (node (ref "LED96") (pin "A") (pinfunction "A_A") (pintype "passive"))
      (node (ref "SV5") (pin "6") (pinfunction "6_6") (pintype "passive"))
    )
    (net (code "9") (name "/L7") (class "Default")
      (node (ref "LED17") (pin "A") (pinfunction "A_A") (pintype "passive"))
      (node (ref "LED27") (pin "A") (pinfunction "A_A") (pintype "passive"))
      (node (ref "LED37") (pin "A") (pinfunction "A_A") (pintype "passive"))
      (node (ref "LED47") (pin "A") (pinfunction "A_A") (pintype "passive"))
      (node (ref "LED57") (pin "A") (pinfunction "A_A") (pintype "passive"))
      (node (ref "LED67") (pin "A") (pinfunction "A_A") (pintype "passive"))
      (node (ref "LED7") (pin "A") (pinfunction "A_A") (pintype "passive"))
      (node (ref "LED77") (pin "A") (pinfunction "A_A") (pintype "passive"))
      (node (ref "LED87") (pin "A") (pinfunction "A_A") (pintype "passive"))
      (node (ref "LED97") (pin "A") (pinfunction "A_A") (pintype "passive"))
      (node (ref "SV5") (pin "7") (pinfunction "7_7") (pintype "passive"))
    )
    (net (code "10") (name "/L8") (class "Default")
      (node (ref "LED18") (pin "A") (pinfunction "A_A") (pintype "passive"))
      (node (ref "LED28") (pin "A") (pinfunction "A_A") (pintype "passive"))
      (node (ref "LED38") (pin "A") (pinfunction "A_A") (pintype "passive"))
      (node (ref "LED48") (pin "A") (pinfunction "A_A") (pintype "passive"))
      (node (ref "LED58") (pin "A") (pinfunction "A_A") (pintype "passive"))
      (node (ref "LED68") (pin "A") (pinfunction "A_A") (pintype "passive"))
      (node (ref "LED78") (pin "A") (pinfunction "A_A") (pintype "passive"))
      (node (ref "LED8") (pin "A") (pinfunction "A_A") (pintype "passive"))
      (node (ref "LED88") (pin "A") (pinfunction "A_A") (pintype "passive"))
      (node (ref "LED98") (pin "A") (pinfunction "A_A") (pintype "passive"))
      (node (ref "SV5") (pin "8") (pinfunction "8_8") (pintype "passive"))
    )
    (net (code "11") (name "/L9") (class "Default")
      (node (ref "LED19") (pin "A") (pinfunction "A_A") (pintype "passive"))
      (node (ref "LED29") (pin "A") (pinfunction "A_A") (pintype "passive"))
      (node (ref "LED39") (pin "A") (pinfunction "A_A") (pintype "passive"))
      (node (ref "LED49") (pin "A") (pinfunction "A_A") (pintype "passive"))
      (node (ref "LED59") (pin "A") (pinfunction "A_A") (pintype "passive"))
      (node (ref "LED69") (pin "A") (pinfunction "A_A") (pintype "passive"))
      (node (ref "LED79") (pin "A") (pinfunction "A_A") (pintype "passive"))
      (node (ref "LED89") (pin "A") (pinfunction "A_A") (pintype "passive"))
      (node (ref "LED9") (pin "A") (pinfunction "A_A") (pintype "passive"))
      (node (ref "LED99") (pin "A") (pinfunction "A_A") (pintype "passive"))
      (node (ref "SV5") (pin "9") (pinfunction "9_9") (pintype "passive"))
    )
    (net (code "12") (name "/L10") (class "Default")
      (node (ref "LED10") (pin "A") (pinfunction "A_A") (pintype "passive"))
      (node (ref "LED100") (pin "A") (pinfunction "A_A") (pintype "passive"))
      (node (ref "LED20") (pin "A") (pinfunction "A_A") (pintype "passive"))
      (node (ref "LED30") (pin "A") (pinfunction "A_A") (pintype "passive"))
      (node (ref "LED40") (pin "A") (pinfunction "A_A") (pintype "passive"))
      (node (ref "LED50") (pin "A") (pinfunction "A_A") (pintype "passive"))
      (node (ref "LED60") (pin "A") (pinfunction "A_A") (pintype "passive"))
      (node (ref "LED70") (pin "A") (pinfunction "A_A") (pintype "passive"))
      (node (ref "LED80") (pin "A") (pinfunction "A_A") (pintype "passive"))
      (node (ref "LED90") (pin "A") (pinfunction "A_A") (pintype "passive"))
      (node (ref "SV5") (pin "10") (pinfunction "10_10") (pintype "passive"))
    )
    (net (code "13") (name "/MISO") (class "Default")
      (node (ref "IC1") (pin "2") (pinfunction "(MISO)PB6_2") (pintype "bidirectional"))
      (node (ref "SV1") (pin "3") (pinfunction "3_3") (pintype "passive"))
    )
    (net (code "14") (name "/MOSI") (class "Default")
      (node (ref "IC1") (pin "1") (pinfunction "(MOSI)PB5_1") (pintype "bidirectional"))
      (node (ref "SV1") (pin "2") (pinfunction "2_2") (pintype "passive"))
    )
    (net (code "15") (name "/N$30") (class "Default")
      (node (ref "R5") (pin "2") (pinfunction "2_2") (pintype "passive"))
      (node (ref "SV3") (pin "1") (pinfunction "1_1") (pintype "passive"))
    )
    (net (code "16") (name "/N$31") (class "Default")
      (node (ref "R2") (pin "2") (pinfunction "2_2") (pintype "passive"))
      (node (ref "SV3") (pin "2") (pinfunction "2_2") (pintype "passive"))
    )
    (net (code "17") (name "/N$32") (class "Default")
      (node (ref "R4") (pin "2") (pinfunction "2_2") (pintype "passive"))
      (node (ref "SV3") (pin "3") (pinfunction "3_3") (pintype "passive"))
    )
    (net (code "18") (name "/N$33") (class "Default")
      (node (ref "R6") (pin "2") (pinfunction "2_2") (pintype "passive"))
      (node (ref "SV3") (pin "4") (pinfunction "4_4") (pintype "passive"))
    )
    (net (code "19") (name "/N$34") (class "Default")
      (node (ref "R7") (pin "2") (pinfunction "2_2") (pintype "passive"))
      (node (ref "SV3") (pin "5") (pinfunction "5_5") (pintype "passive"))
    )
    (net (code "20") (name "/N$35") (class "Default")
      (node (ref "R8") (pin "2") (pinfunction "2_2") (pintype "passive"))
      (node (ref "SV3") (pin "6") (pinfunction "6_6") (pintype "passive"))
    )
    (net (code "21") (name "/N$36") (class "Default")
      (node (ref "R9") (pin "2") (pinfunction "2_2") (pintype "passive"))
      (node (ref "SV3") (pin "7") (pinfunction "7_7") (pintype "passive"))
    )
    (net (code "22") (name "/N$37") (class "Default")
      (node (ref "R10") (pin "2") (pinfunction "2_2") (pintype "passive"))
      (node (ref "SV3") (pin "8") (pinfunction "8_8") (pintype "passive"))
    )
    (net (code "23") (name "/N$38") (class "Default")
      (node (ref "R13") (pin "2") (pinfunction "2_2") (pintype "passive"))
      (node (ref "SV3") (pin "9") (pinfunction "9_9") (pintype "passive"))
    )
    (net (code "24") (name "/N$39") (class "Default")
      (node (ref "R14") (pin "2") (pinfunction "2_2") (pintype "passive"))
      (node (ref "SV3") (pin "10") (pinfunction "10_10") (pintype "passive"))
    )
    (net (code "25") (name "/N$40") (class "Default")
      (node (ref "R15") (pin "2") (pinfunction "2_2") (pintype "passive"))
      (node (ref "SV4") (pin "9") (pinfunction "9_9") (pintype "passive"))
    )
    (net (code "26") (name "/N$41") (class "Default")
      (node (ref "R16") (pin "2") (pinfunction "2_2") (pintype "passive"))
      (node (ref "SV4") (pin "10") (pinfunction "10_10") (pintype "passive"))
    )
    (net (code "27") (name "/N$42") (class "Default")
      (node (ref "R17") (pin "2") (pinfunction "2_2") (pintype "passive"))
      (node (ref "SV4") (pin "3") (pinfunction "3_3") (pintype "passive"))
    )
    (net (code "28") (name "/N$43") (class "Default")
      (node (ref "R18") (pin "2") (pinfunction "2_2") (pintype "passive"))
      (node (ref "SV4") (pin "4") (pinfunction "4_4") (pintype "passive"))
    )
    (net (code "29") (name "/N$44") (class "Default")
      (node (ref "R19") (pin "2") (pinfunction "2_2") (pintype "passive"))
      (node (ref "SV4") (pin "1") (pinfunction "1_1") (pintype "passive"))
    )
    (net (code "30") (name "/N$45") (class "Default")
      (node (ref "R20") (pin "2") (pinfunction "2_2") (pintype "passive"))
      (node (ref "SV4") (pin "2") (pinfunction "2_2") (pintype "passive"))
    )
    (net (code "31") (name "/N$46") (class "Default")
      (node (ref "R21") (pin "2") (pinfunction "2_2") (pintype "passive"))
      (node (ref "SV4") (pin "7") (pinfunction "7_7") (pintype "passive"))
    )
    (net (code "32") (name "/N$47") (class "Default")
      (node (ref "R22") (pin "2") (pinfunction "2_2") (pintype "passive"))
      (node (ref "SV4") (pin "8") (pinfunction "8_8") (pintype "passive"))
    )
    (net (code "33") (name "/N$48") (class "Default")
      (node (ref "R11") (pin "2") (pinfunction "2_2") (pintype "passive"))
      (node (ref "SV4") (pin "5") (pinfunction "5_5") (pintype "passive"))
    )
    (net (code "34") (name "/N$49") (class "Default")
      (node (ref "R12") (pin "2") (pinfunction "2_2") (pintype "passive"))
      (node (ref "SV4") (pin "6") (pinfunction "6_6") (pintype "passive"))
    )
    (net (code "35") (name "/R1") (class "Default")
      (node (ref "LED51") (pin "C") (pinfunction "C_C") (pintype "passive"))
      (node (ref "LED52") (pin "C") (pinfunction "C_C") (pintype "passive"))
      (node (ref "LED53") (pin "C") (pinfunction "C_C") (pintype "passive"))
      (node (ref "LED54") (pin "C") (pinfunction "C_C") (pintype "passive"))
      (node (ref "LED55") (pin "C") (pinfunction "C_C") (pintype "passive"))
      (node (ref "LED56") (pin "C") (pinfunction "C_C") (pintype "passive"))
      (node (ref "LED57") (pin "C") (pinfunction "C_C") (pintype "passive"))
      (node (ref "LED58") (pin "C") (pinfunction "C_C") (pintype "passive"))
      (node (ref "LED59") (pin "C") (pinfunction "C_C") (pintype "passive"))
      (node (ref "LED60") (pin "C") (pinfunction "C_C") (pintype "passive"))
      (node (ref "SV7") (pin "6") (pinfunction "6_6") (pintype "passive"))
    )
    (net (code "36") (name "/R2") (class "Default")
      (node (ref "LED71") (pin "C") (pinfunction "C_C") (pintype "passive"))
      (node (ref "LED72") (pin "C") (pinfunction "C_C") (pintype "passive"))
      (node (ref "LED73") (pin "C") (pinfunction "C_C") (pintype "passive"))
      (node (ref "LED74") (pin "C") (pinfunction "C_C") (pintype "passive"))
      (node (ref "LED75") (pin "C") (pinfunction "C_C") (pintype "passive"))
      (node (ref "LED76") (pin "C") (pinfunction "C_C") (pintype "passive"))
      (node (ref "LED77") (pin "C") (pinfunction "C_C") (pintype "passive"))
      (node (ref "LED78") (pin "C") (pinfunction "C_C") (pintype "passive"))
      (node (ref "LED79") (pin "C") (pinfunction "C_C") (pintype "passive"))
      (node (ref "LED80") (pin "C") (pinfunction "C_C") (pintype "passive"))
      (node (ref "SV7") (pin "10") (pinfunction "10_10") (pintype "passive"))
    )
    (net (code "37") (name "/R3") (class "Default")
      (node (ref "LED41") (pin "C") (pinfunction "C_C") (pintype "passive"))
      (node (ref "LED42") (pin "C") (pinfunction "C_C") (pintype "passive"))
      (node (ref "LED43") (pin "C") (pinfunction "C_C") (pintype "passive"))
      (node (ref "LED44") (pin "C") (pinfunction "C_C") (pintype "passive"))
      (node (ref "LED45") (pin "C") (pinfunction "C_C") (pintype "passive"))
      (node (ref "LED46") (pin "C") (pinfunction "C_C") (pintype "passive"))
      (node (ref "LED47") (pin "C") (pinfunction "C_C") (pintype "passive"))
      (node (ref "LED48") (pin "C") (pinfunction "C_C") (pintype "passive"))
      (node (ref "LED49") (pin "C") (pinfunction "C_C") (pintype "passive"))
      (node (ref "LED50") (pin "C") (pinfunction "C_C") (pintype "passive"))
      (node (ref "SV7") (pin "5") (pinfunction "5_5") (pintype "passive"))
    )
    (net (code "38") (name "/R4") (class "Default")
      (node (ref "LED61") (pin "C") (pinfunction "C_C") (pintype "passive"))
      (node (ref "LED62") (pin "C") (pinfunction "C_C") (pintype "passive"))
      (node (ref "LED63") (pin "C") (pinfunction "C_C") (pintype "passive"))
      (node (ref "LED64") (pin "C") (pinfunction "C_C") (pintype "passive"))
      (node (ref "LED65") (pin "C") (pinfunction "C_C") (pintype "passive"))
      (node (ref "LED66") (pin "C") (pinfunction "C_C") (pintype "passive"))
      (node (ref "LED67") (pin "C") (pinfunction "C_C") (pintype "passive"))
      (node (ref "LED68") (pin "C") (pinfunction "C_C") (pintype "passive"))
      (node (ref "LED69") (pin "C") (pinfunction "C_C") (pintype "passive"))
      (node (ref "LED70") (pin "C") (pinfunction "C_C") (pintype "passive"))
      (node (ref "SV7") (pin "9") (pinfunction "9_9") (pintype "passive"))
    )
    (net (code "39") (name "/R5") (class "Default")
      (node (ref "LED11") (pin "C") (pinfunction "C_C") (pintype "passive"))
      (node (ref "LED12") (pin "C") (pinfunction "C_C") (pintype "passive"))
      (node (ref "LED13") (pin "C") (pinfunction "C_C") (pintype "passive"))
      (node (ref "LED14") (pin "C") (pinfunction "C_C") (pintype "passive"))
      (node (ref "LED15") (pin "C") (pinfunction "C_C") (pintype "passive"))
      (node (ref "LED16") (pin "C") (pinfunction "C_C") (pintype "passive"))
      (node (ref "LED17") (pin "C") (pinfunction "C_C") (pintype "passive"))
      (node (ref "LED18") (pin "C") (pinfunction "C_C") (pintype "passive"))
      (node (ref "LED19") (pin "C") (pinfunction "C_C") (pintype "passive"))
      (node (ref "LED20") (pin "C") (pinfunction "C_C") (pintype "passive"))
      (node (ref "SV7") (pin "2") (pinfunction "2_2") (pintype "passive"))
    )
    (net (code "40") (name "/R6") (class "Default")
      (node (ref "LED31") (pin "C") (pinfunction "C_C") (pintype "passive"))
      (node (ref "LED32") (pin "C") (pinfunction "C_C") (pintype "passive"))
      (node (ref "LED33") (pin "C") (pinfunction "C_C") (pintype "passive"))
      (node (ref "LED34") (pin "C") (pinfunction "C_C") (pintype "passive"))
      (node (ref "LED35") (pin "C") (pinfunction "C_C") (pintype "passive"))
      (node (ref "LED36") (pin "C") (pinfunction "C_C") (pintype "passive"))
      (node (ref "LED37") (pin "C") (pinfunction "C_C") (pintype "passive"))
      (node (ref "LED38") (pin "C") (pinfunction "C_C") (pintype "passive"))
      (node (ref "LED39") (pin "C") (pinfunction "C_C") (pintype "passive"))
      (node (ref "LED40") (pin "C") (pinfunction "C_C") (pintype "passive"))
      (node (ref "SV7") (pin "4") (pinfunction "4_4") (pintype "passive"))
    )
    (net (code "41") (name "/R7") (class "Default")
      (node (ref "LED1") (pin "C") (pinfunction "C_C") (pintype "passive"))
      (node (ref "LED10") (pin "C") (pinfunction "C_C") (pintype "passive"))
      (node (ref "LED2") (pin "C") (pinfunction "C_C") (pintype "passive"))
      (node (ref "LED3") (pin "C") (pinfunction "C_C") (pintype "passive"))
      (node (ref "LED4") (pin "C") (pinfunction "C_C") (pintype "passive"))
      (node (ref "LED5") (pin "C") (pinfunction "C_C") (pintype "passive"))
      (node (ref "LED6") (pin "C") (pinfunction "C_C") (pintype "passive"))
      (node (ref "LED7") (pin "C") (pinfunction "C_C") (pintype "passive"))
      (node (ref "LED8") (pin "C") (pinfunction "C_C") (pintype "passive"))
      (node (ref "LED9") (pin "C") (pinfunction "C_C") (pintype "passive"))
      (node (ref "SV7") (pin "1") (pinfunction "1_1") (pintype "passive"))
    )
    (net (code "42") (name "/R8") (class "Default")
      (node (ref "LED21") (pin "C") (pinfunction "C_C") (pintype "passive"))
      (node (ref "LED22") (pin "C") (pinfunction "C_C") (pintype "passive"))
      (node (ref "LED23") (pin "C") (pinfunction "C_C") (pintype "passive"))
      (node (ref "LED24") (pin "C") (pinfunction "C_C") (pintype "passive"))
      (node (ref "LED25") (pin "C") (pinfunction "C_C") (pintype "passive"))
      (node (ref "LED26") (pin "C") (pinfunction "C_C") (pintype "passive"))
      (node (ref "LED27") (pin "C") (pinfunction "C_C") (pintype "passive"))
      (node (ref "LED28") (pin "C") (pinfunction "C_C") (pintype "passive"))
      (node (ref "LED29") (pin "C") (pinfunction "C_C") (pintype "passive"))
      (node (ref "LED30") (pin "C") (pinfunction "C_C") (pintype "passive"))
      (node (ref "SV7") (pin "3") (pinfunction "3_3") (pintype "passive"))
    )
    (net (code "43") (name "/R9") (class "Default")
      (node (ref "LED81") (pin "C") (pinfunction "C_C") (pintype "passive"))
      (node (ref "LED82") (pin "C") (pinfunction "C_C") (pintype "passive"))
      (node (ref "LED83") (pin "C") (pinfunction "C_C") (pintype "passive"))
      (node (ref "LED84") (pin "C") (pinfunction "C_C") (pintype "passive"))
      (node (ref "LED85") (pin "C") (pinfunction "C_C") (pintype "passive"))
      (node (ref "LED86") (pin "C") (pinfunction "C_C") (pintype "passive"))
      (node (ref "LED87") (pin "C") (pinfunction "C_C") (pintype "passive"))
      (node (ref "LED88") (pin "C") (pinfunction "C_C") (pintype "passive"))
      (node (ref "LED89") (pin "C") (pinfunction "C_C") (pintype "passive"))
      (node (ref "LED90") (pin "C") (pinfunction "C_C") (pintype "passive"))
      (node (ref "SV7") (pin "8") (pinfunction "8_8") (pintype "passive"))
    )
    (net (code "44") (name "/R10") (class "Default")
      (node (ref "LED100") (pin "C") (pinfunction "C_C") (pintype "passive"))
      (node (ref "LED91") (pin "C") (pinfunction "C_C") (pintype "passive"))
      (node (ref "LED92") (pin "C") (pinfunction "C_C") (pintype "passive"))
      (node (ref "LED93") (pin "C") (pinfunction "C_C") (pintype "passive"))
      (node (ref "LED94") (pin "C") (pinfunction "C_C") (pintype "passive"))
      (node (ref "LED95") (pin "C") (pinfunction "C_C") (pintype "passive"))
      (node (ref "LED96") (pin "C") (pinfunction "C_C") (pintype "passive"))
      (node (ref "LED97") (pin "C") (pinfunction "C_C") (pintype "passive"))
      (node (ref "LED98") (pin "C") (pinfunction "C_C") (pintype "passive"))
      (node (ref "LED99") (pin "C") (pinfunction "C_C") (pintype "passive"))
      (node (ref "SV7") (pin "7") (pinfunction "7_7") (pintype "passive"))
    )
    (net (code "45") (name "/RST") (class "Default")
      (node (ref "C4") (pin "+") (pinfunction "+_+") (pintype "passive"))
      (node (ref "IC1") (pin "4") (pinfunction "RESET_4") (pintype "input"))
      (node (ref "R3") (pin "1") (pinfunction "1_1") (pintype "passive"))
      (node (ref "S1") (pin "P$1") (pinfunction "1_P$1") (pintype "passive"))
      (node (ref "SV1") (pin "5") (pinfunction "5_5") (pintype "passive"))
    )
    (net (code "46") (name "/SCL") (class "Default")
      (node (ref "IC1") (pin "10") (pinfunction "(TXD)PD1_10") (pintype "bidirectional"))
      (node (ref "IC1") (pin "19") (pinfunction "PC0(SCL)_19") (pintype "bidirectional"))
      (node (ref "SV6") (pin "3") (pinfunction "3_3") (pintype "passive"))
    )
    (net (code "47") (name "/SDA") (class "Default")
      (node (ref "IC1") (pin "20") (pinfunction "PC1(SDA)_20") (pintype "bidirectional"))
      (node (ref "IC1") (pin "9") (pinfunction "(RXD)PD0_9") (pintype "bidirectional"))
      (node (ref "SV6") (pin "2") (pinfunction "2_2") (pintype "passive"))
    )
    (net (code "48") (name "/VC") (class "Default")
      (node (ref "IC1") (pin "17") (pinfunction "VCC1_17") (pintype "power_in"))
      (node (ref "IC1") (pin "27") (pinfunction "AVCC_27") (pintype "power_in"))
      (node (ref "IC1") (pin "38") (pinfunction "VCC2_38") (pintype "power_in"))
      (node (ref "IC1") (pin "5") (pinfunction "VCC_5") (pintype "power_in"))
      (node (ref "IC2") (pin "2") (pinfunction "VO_2") (pintype "passive"))
      (node (ref "R1") (pin "1") (pinfunction "E_1") (pintype "passive"))
      (node (ref "R3") (pin "2") (pinfunction "2_2") (pintype "passive"))
      (node (ref "SV1") (pin "6") (pinfunction "6_6") (pintype "passive"))
    )
    (net (code "49") (name "Net-(IC1-(ADC0)PA0)") (class "Default")
      (node (ref "IC1") (pin "37") (pinfunction "(ADC0)PA0_37") (pintype "bidirectional"))
      (node (ref "R9") (pin "1") (pinfunction "1_1") (pintype "passive"))
    )
    (net (code "50") (name "Net-(IC1-(ADC1)PA1)") (class "Default")
      (node (ref "IC1") (pin "36") (pinfunction "(ADC1)PA1_36") (pintype "bidirectional"))
      (node (ref "R8") (pin "1") (pinfunction "1_1") (pintype "passive"))
    )
    (net (code "51") (name "Net-(IC1-(ADC2)PA2)") (class "Default")
      (node (ref "IC1") (pin "35") (pinfunction "(ADC2)PA2_35") (pintype "bidirectional"))
      (node (ref "R7") (pin "1") (pinfunction "1_1") (pintype "passive"))
    )
    (net (code "52") (name "Net-(IC1-(ADC3)PA3)") (class "Default")
      (node (ref "IC1") (pin "34") (pinfunction "(ADC3)PA3_34") (pintype "bidirectional"))
      (node (ref "R6") (pin "1") (pinfunction "1_1") (pintype "passive"))
    )
    (net (code "53") (name "Net-(IC1-(ADC4)PA4)") (class "Default")
      (node (ref "IC1") (pin "33") (pinfunction "(ADC4)PA4_33") (pintype "bidirectional"))
      (node (ref "R1") (pin "2") (pinfunction "S_2") (pintype "passive"))
    )
    (net (code "54") (name "Net-(IC1-(ADC5)PA5)") (class "Default")
      (node (ref "IC1") (pin "32") (pinfunction "(ADC5)PA5_32") (pintype "bidirectional"))
      (node (ref "R4") (pin "1") (pinfunction "1_1") (pintype "passive"))
    )
    (net (code "55") (name "Net-(IC1-(ADC6)PA6)") (class "Default")
      (node (ref "IC1") (pin "31") (pinfunction "(ADC6)PA6_31") (pintype "bidirectional"))
      (node (ref "R2") (pin "1") (pinfunction "1_1") (pintype "passive"))
    )
    (net (code "56") (name "Net-(IC1-(ADC7)PA7)") (class "Default")
      (node (ref "IC1") (pin "30") (pinfunction "(ADC7)PA7_30") (pintype "bidirectional"))
      (node (ref "R5") (pin "1") (pinfunction "1_1") (pintype "passive"))
    )
    (net (code "57") (name "Net-(IC1-(AIN0{slash}INT2)PB2)") (class "Default")
      (node (ref "IC1") (pin "42") (pinfunction "(AIN0/INT2)PB2_42") (pintype "bidirectional"))
      (node (ref "R14") (pin "1") (pinfunction "1_1") (pintype "passive"))
    )
    (net (code "58") (name "Net-(IC1-(AIN1{slash}OC0)PB3)") (class "Default")
      (node (ref "IC1") (pin "43") (pinfunction "(AIN1/OC0)PB3_43") (pintype "bidirectional"))
      (node (ref "R13") (pin "1") (pinfunction "1_1") (pintype "passive"))
    )
    (net (code "59") (name "Net-(IC1-(ICP)PD6)") (class "Default")
      (node (ref "IC1") (pin "15") (pinfunction "(ICP)PD6_15") (pintype "bidirectional"))
      (node (ref "R12") (pin "1") (pinfunction "1_1") (pintype "passive"))
    )
    (net (code "60") (name "Net-(IC1-(INT1)PD3)") (class "Default")
      (node (ref "IC1") (pin "12") (pinfunction "(INT1)PD3_12") (pintype "bidirectional"))
      (node (ref "S2") (pin "P$2") (pinfunction "2_P$2") (pintype "passive"))
    )
    (net (code "61") (name "Net-(IC1-(OC2)PD7)") (class "Default")
      (node (ref "IC1") (pin "16") (pinfunction "(OC2)PD7_16") (pintype "bidirectional"))
      (node (ref "R11") (pin "1") (pinfunction "1_1") (pintype "passive"))
    )
    (net (code "62") (name "Net-(IC1-(SS)PB4)") (class "Default")
      (node (ref "IC1") (pin "44") (pinfunction "(SS)PB4_44") (pintype "bidirectional"))
      (node (ref "R10") (pin "1") (pinfunction "1_1") (pintype "passive"))
    )
    (net (code "63") (name "Net-(IC1-(T0{slash}XCK)PB0)") (class "Default")
      (node (ref "IC1") (pin "40") (pinfunction "(T0/XCK)PB0_40") (pintype "bidirectional"))
      (node (ref "R16") (pin "1") (pinfunction "1_1") (pintype "passive"))
    )
    (net (code "64") (name "Net-(IC1-(T1)PB1)") (class "Default")
      (node (ref "IC1") (pin "41") (pinfunction "(T1)PB1_41") (pintype "bidirectional"))
      (node (ref "R15") (pin "1") (pinfunction "1_1") (pintype "passive"))
    )
    (net (code "65") (name "Net-(IC1-(TCK)PC2)") (class "Default")
      (node (ref "IC1") (pin "21") (pinfunction "(TCK)PC2_21") (pintype "bidirectional"))
      (node (ref "R22") (pin "1") (pinfunction "1_1") (pintype "passive"))
    )
    (net (code "66") (name "Net-(IC1-(TDI)PC5)") (class "Default")
      (node (ref "IC1") (pin "24") (pinfunction "(TDI)PC5_24") (pintype "bidirectional"))
      (node (ref "R19") (pin "1") (pinfunction "1_1") (pintype "passive"))
    )
    (net (code "67") (name "Net-(IC1-(TDO)PC4)") (class "Default")
      (node (ref "IC1") (pin "23") (pinfunction "(TDO)PC4_23") (pintype "bidirectional"))
      (node (ref "R20") (pin "1") (pinfunction "1_1") (pintype "passive"))
    )
    (net (code "68") (name "Net-(IC1-(TMS)PC3)") (class "Default")
      (node (ref "IC1") (pin "22") (pinfunction "(TMS)PC3_22") (pintype "bidirectional"))
      (node (ref "R21") (pin "1") (pinfunction "1_1") (pintype "passive"))
    )
    (net (code "69") (name "Net-(IC1-(TOSC1)PC6)") (class "Default")
      (node (ref "IC1") (pin "25") (pinfunction "(TOSC1)PC6_25") (pintype "bidirectional"))
      (node (ref "R18") (pin "1") (pinfunction "1_1") (pintype "passive"))
    )
    (net (code "70") (name "Net-(IC1-(TOSC2)PC7)") (class "Default")
      (node (ref "IC1") (pin "26") (pinfunction "(TOSC2)PC7_26") (pintype "bidirectional"))
      (node (ref "R17") (pin "1") (pinfunction "1_1") (pintype "passive"))
    )
    (net (code "71") (name "Net-(IC1-XTAL1)") (class "Default")
      (node (ref "C2") (pin "1") (pinfunction "1_1") (pintype "passive"))
      (node (ref "IC1") (pin "8") (pinfunction "XTAL1_8") (pintype "bidirectional"))
      (node (ref "Q2") (pin "1") (pinfunction "1_1") (pintype "passive"))
    )
    (net (code "72") (name "Net-(IC1-XTAL2)") (class "Default")
      (node (ref "C1") (pin "1") (pinfunction "1_1") (pintype "passive"))
      (node (ref "IC1") (pin "7") (pinfunction "XTAL2_7") (pintype "bidirectional"))
      (node (ref "Q2") (pin "2") (pinfunction "2_2") (pintype "passive"))
    )
    (net (code "73") (name "Net-(IC2-VI)") (class "Default")
      (node (ref "IC2") (pin "1") (pinfunction "VI_1") (pintype "input"))
      (node (ref "SV2") (pin "1") (pinfunction "1_1") (pintype "passive"))
    )
    (net (code "74") (name "unconnected-(IC1-(INT0)PD2-Pad11)") (class "Default")
      (node (ref "IC1") (pin "11") (pinfunction "(INT0)PD2_11") (pintype "bidirectional"))
    )
    (net (code "75") (name "unconnected-(IC1-(OC1A)PD5-Pad14)") (class "Default")
      (node (ref "IC1") (pin "14") (pinfunction "(OC1A)PD5_14") (pintype "bidirectional"))
    )
    (net (code "76") (name "unconnected-(IC1-(OC1B)PD4-Pad13)") (class "Default")
      (node (ref "IC1") (pin "13") (pinfunction "(OC1B)PD4_13") (pintype "bidirectional"))
    )
    (net (code "77") (name "unconnected-(IC1-AREF-Pad29)") (class "Default")
      (node (ref "IC1") (pin "29") (pinfunction "AREF_29") (pintype "passive"))
    )
    (net (code "78") (name "unconnected-(SV2-Pad2)") (class "Default")
      (node (ref "SV2") (pin "2") (pinfunction "2_2") (pintype "passive"))
    )
  )
)
